# 15-Sensors.net
KiCad netlist of a schematic drawn in Altium Designer
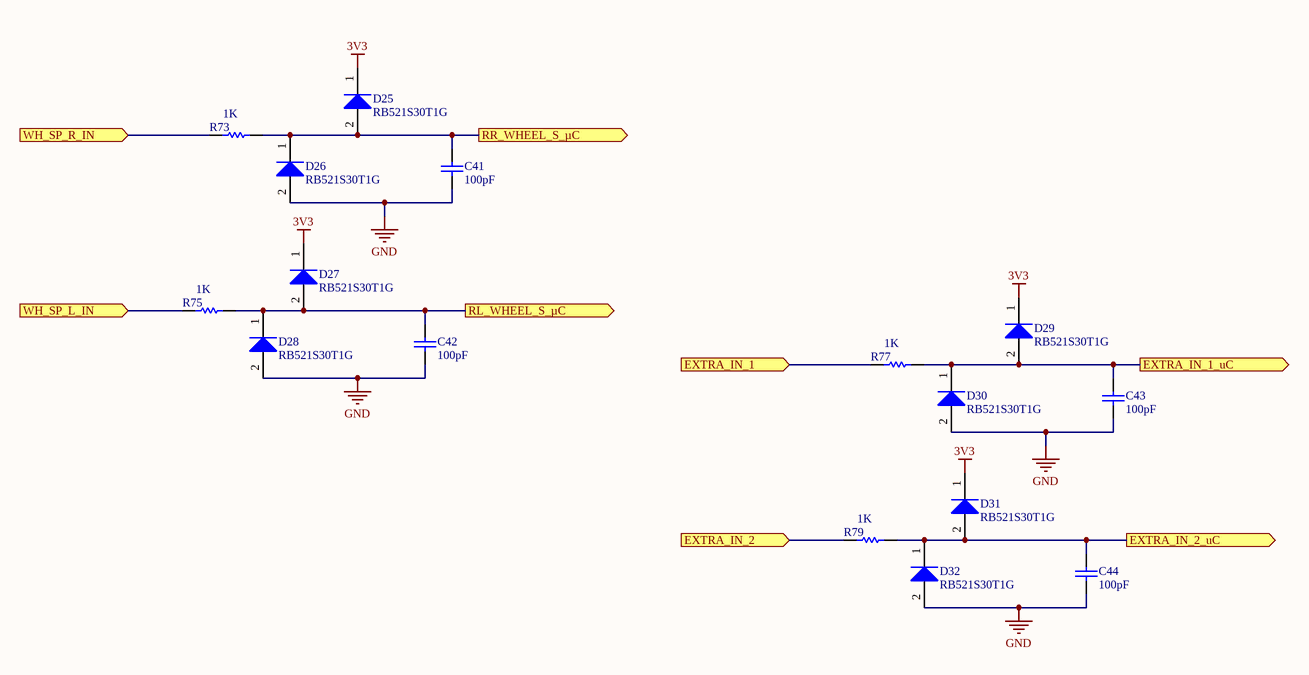
[diagram p0: 15-Sensors.SchDoc]

(export (version "E")
  (design (tool "Eeschema 10.0.6"))
  (components
    (comp (ref "C41")
      (value "100pF")
      (footprint "1608[0603]")
      (description "Capacitor")
      (fields (field (name "Comment") "Cap") (field (name "PUBLISHER") "Altium Limited"))
      (libsource (lib "Miscellaneous Devices") (part "Cap"))
    )
    (comp (ref "C42")
      (value "100pF")
      (footprint "1608[0603]")
      (description "Capacitor")
      (fields (field (name "Comment") "Cap") (field (name "PUBLISHER") "Altium Limited"))
      (libsource (lib "Miscellaneous Devices") (part "Cap"))
    )
    (comp (ref "C43")
      (value "100pF")
      (footprint "1608[0603]")
      (description "Capacitor")
      (fields (field (name "Comment") "Cap") (field (name "PUBLISHER") "Altium Limited"))
      (libsource (lib "Miscellaneous Devices") (part "Cap"))
    )
    (comp (ref "C44")
      (value "100pF")
      (footprint "1608[0603]")
      (description "Capacitor")
      (fields (field (name "Comment") "Cap") (field (name "PUBLISHER") "Altium Limited"))
      (libsource (lib "Miscellaneous Devices") (part "Cap"))
    )
    (comp (ref "D25")
      (value "RB521S30T1G")
      (footprint "ONSC-SOD-523-2-502-01_V")
      (description "Schottky Barrier Diode, 2-Pin SOD-523, Pb-Free, Tape and Reel")
      (fields (field (name "MANUFACTURER") "On Semiconductor"))
      (libsource (lib "Altium Content Vault") (part "ONSC-D-K1A2-2"))
    )
    (comp (ref "D26")
      (value "RB521S30T1G")
      (footprint "ONSC-SOD-523-2-502-01_V")
      (description "Schottky Barrier Diode, 2-Pin SOD-523, Pb-Free, Tape and Reel")
      (fields (field (name "MANUFACTURER") "On Semiconductor"))
      (libsource (lib "Altium Content Vault") (part "ONSC-D-K1A2-2"))
    )
    (comp (ref "D27")
      (value "RB521S30T1G")
      (footprint "ONSC-SOD-523-2-502-01_V")
      (description "Schottky Barrier Diode, 2-Pin SOD-523, Pb-Free, Tape and Reel")
      (fields (field (name "MANUFACTURER") "On Semiconductor"))
      (libsource (lib "Altium Content Vault") (part "ONSC-D-K1A2-2"))
    )
    (comp (ref "D28")
      (value "RB521S30T1G")
      (footprint "ONSC-SOD-523-2-502-01_V")
      (description "Schottky Barrier Diode, 2-Pin SOD-523, Pb-Free, Tape and Reel")
      (fields (field (name "MANUFACTURER") "On Semiconductor"))
      (libsource (lib "Altium Content Vault") (part "ONSC-D-K1A2-2"))
    )
    (comp (ref "D29")
      (value "RB521S30T1G")
      (footprint "ONSC-SOD-523-2-502-01_V")
      (description "Schottky Barrier Diode, 2-Pin SOD-523, Pb-Free, Tape and Reel")
      (fields (field (name "MANUFACTURER") "On Semiconductor"))
      (libsource (lib "Altium Content Vault") (part "ONSC-D-K1A2-2"))
    )
    (comp (ref "D30")
      (value "RB521S30T1G")
      (footprint "ONSC-SOD-523-2-502-01_V")
      (description "Schottky Barrier Diode, 2-Pin SOD-523, Pb-Free, Tape and Reel")
      (fields (field (name "MANUFACTURER") "On Semiconductor"))
      (libsource (lib "Altium Content Vault") (part "ONSC-D-K1A2-2"))
    )
    (comp (ref "D31")
      (value "RB521S30T1G")
      (footprint "ONSC-SOD-523-2-502-01_V")
      (description "Schottky Barrier Diode, 2-Pin SOD-523, Pb-Free, Tape and Reel")
      (fields (field (name "MANUFACTURER") "On Semiconductor"))
      (libsource (lib "Altium Content Vault") (part "ONSC-D-K1A2-2"))
    )
    (comp (ref "D32")
      (value "RB521S30T1G")
      (footprint "ONSC-SOD-523-2-502-01_V")
      (description "Schottky Barrier Diode, 2-Pin SOD-523, Pb-Free, Tape and Reel")
      (fields (field (name "MANUFACTURER") "On Semiconductor"))
      (libsource (lib "Altium Content Vault") (part "ONSC-D-K1A2-2"))
    )
    (comp (ref "R73")
      (value "1K")
      (footprint "1608[0603]")
      (description "Resistor")
      (fields (field (name "Comment") "Res1") (field (name "PUBLISHER") "Altium Limited"))
      (libsource (lib "Miscellaneous Devices") (part "Res1"))
    )
    (comp (ref "R75")
      (value "1K")
      (footprint "1608[0603]")
      (description "Resistor")
      (fields (field (name "Comment") "Res1") (field (name "PUBLISHER") "Altium Limited"))
      (libsource (lib "Miscellaneous Devices") (part "Res1"))
    )
    (comp (ref "R77")
      (value "1K")
      (footprint "1608[0603]")
      (description "Resistor")
      (fields (field (name "Comment") "Res1") (field (name "PUBLISHER") "Altium Limited"))
      (libsource (lib "Miscellaneous Devices") (part "Res1"))
    )
    (comp (ref "R79")
      (value "1K")
      (footprint "1608[0603]")
      (description "Resistor")
      (fields (field (name "Comment") "Res1") (field (name "PUBLISHER") "Altium Limited"))
      (libsource (lib "Miscellaneous Devices") (part "Res1"))
    )
  )
  (nets
    (net (code "1") (name "/EXTRA_IN_1") (class "Default")
      (node (ref "R77") (pin "1") (pinfunction "1_1") (pintype "passive"))
    )
    (net (code "2") (name "/EXTRA_IN_1_uC") (class "Default")
      (node (ref "C43") (pin "2") (pinfunction "2_2") (pintype "passive"))
      (node (ref "D29") (pin "2") (pinfunction "A_2") (pintype "passive"))
      (node (ref "D30") (pin "1") (pinfunction "K_1") (pintype "passive"))
      (node (ref "R77") (pin "2") (pinfunction "2_2") (pintype "passive"))
    )
    (net (code "3") (name "/EXTRA_IN_2") (class "Default")
      (node (ref "R79") (pin "1") (pinfunction "1_1") (pintype "passive"))
    )
    (net (code "4") (name "/EXTRA_IN_2_uC") (class "Default")
      (node (ref "C44") (pin "2") (pinfunction "2_2") (pintype "passive"))
      (node (ref "D31") (pin "2") (pinfunction "A_2") (pintype "passive"))
      (node (ref "D32") (pin "1") (pinfunction "K_1") (pintype "passive"))
      (node (ref "R79") (pin "2") (pinfunction "2_2") (pintype "passive"))
    )
    (net (code "5") (name "/RL_WHEEL_S_µC") (class "Default")
      (node (ref "C42") (pin "2") (pinfunction "2_2") (pintype "passive"))
      (node (ref "D27") (pin "2") (pinfunction "A_2") (pintype "passive"))
      (node (ref "D28") (pin "1") (pinfunction "K_1") (pintype "passive"))
      (node (ref "R75") (pin "2") (pinfunction "2_2") (pintype "passive"))
    )
    (net (code "6") (name "/RR_WHEEL_S_µC") (class "Default")
      (node (ref "C41") (pin "2") (pinfunction "2_2") (pintype "passive"))
      (node (ref "D25") (pin "2") (pinfunction "A_2") (pintype "passive"))
      (node (ref "D26") (pin "1") (pinfunction "K_1") (pintype "passive"))
      (node (ref "R73") (pin "2") (pinfunction "2_2") (pintype "passive"))
    )
    (net (code "7") (name "/WH_SP_L_IN") (class "Default")
      (node (ref "R75") (pin "1") (pinfunction "1_1") (pintype "passive"))
    )
    (net (code "8") (name "/WH_SP_R_IN") (class "Default")
      (node (ref "R73") (pin "1") (pinfunction "1_1") (pintype "passive"))
    )
    (net (code "9") (name "3V3") (class "Default")
      (node (ref "D25") (pin "1") (pinfunction "K_1") (pintype "passive"))
      (node (ref "D27") (pin "1") (pinfunction "K_1") (pintype "passive"))
      (node (ref "D29") (pin "1") (pinfunction "K_1") (pintype "passive"))
      (node (ref "D31") (pin "1") (pinfunction "K_1") (pintype "passive"))
    )
    (net (code "10") (name "GND") (class "Default")
      (node (ref "C41") (pin "1") (pinfunction "1_1") (pintype "passive"))
      (node (ref "C42") (pin "1") (pinfunction "1_1") (pintype "passive"))
      (node (ref "C43") (pin "1") (pinfunction "1_1") (pintype "passive"))
      (node (ref "C44") (pin "1") (pinfunction "1_1") (pintype "passive"))
      (node (ref "D26") (pin "2") (pinfunction "A_2") (pintype "passive"))
      (node (ref "D28") (pin "2") (pinfunction "A_2") (pintype "passive"))
      (node (ref "D30") (pin "2") (pinfunction "A_2") (pintype "passive"))
      (node (ref "D32") (pin "2") (pinfunction "A_2") (pintype "passive"))
    )
  )
)
